# 12V_Converter.net
KiCad netlist of a schematic drawn in Altium Designer
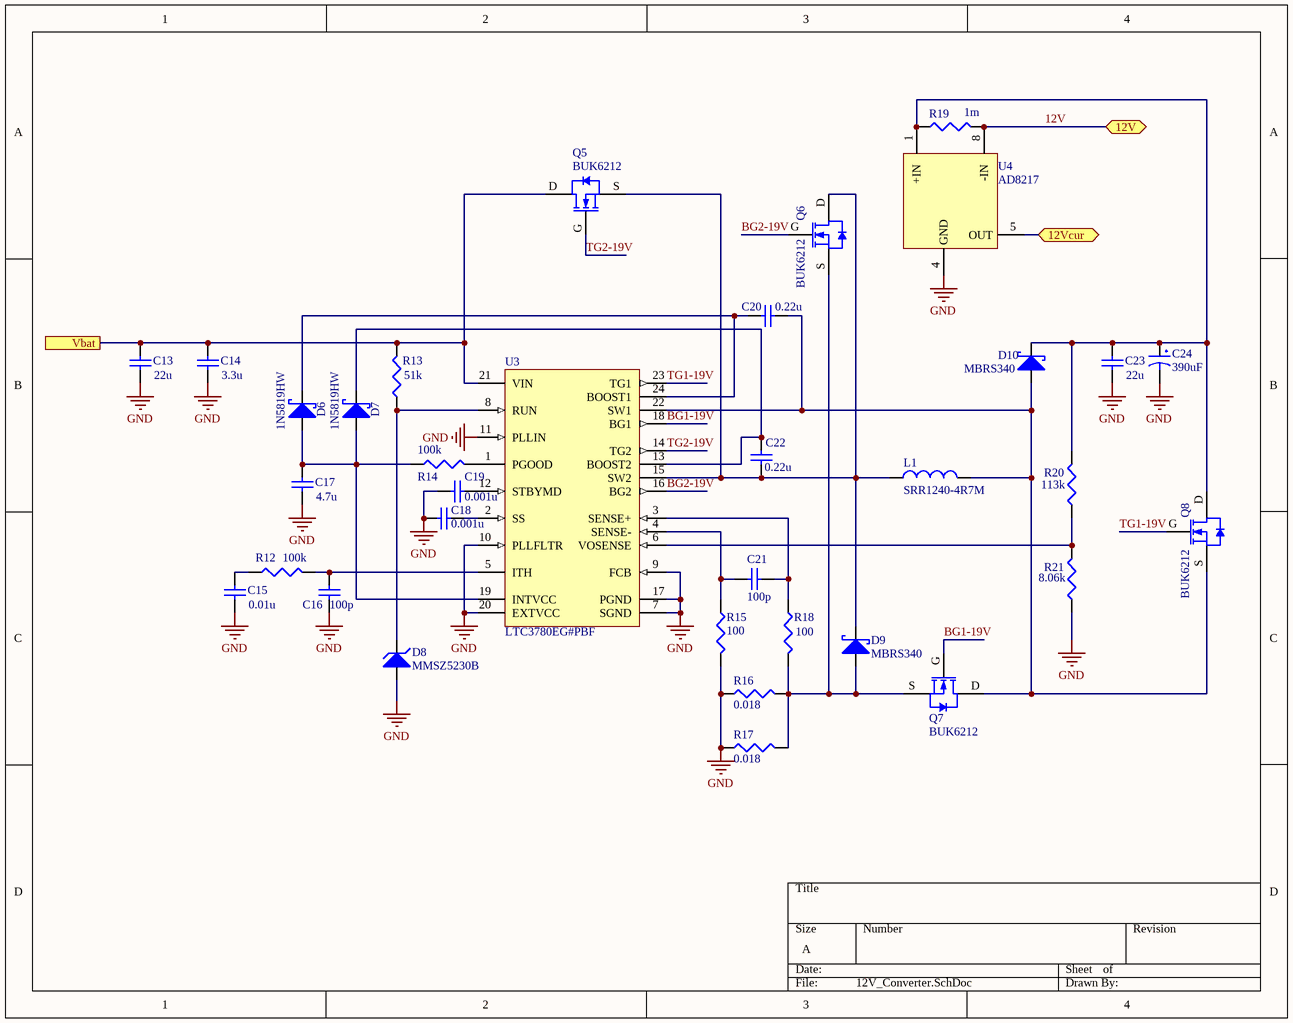
[diagram p0: 12V_Converter.SchDoc]

(export (version "E")
  (design (tool "Eeschema 10.0.6"))
  (components
    (comp (ref "C13")
      (value "22u")
      (footprint "C1206")
      (description "Capacitor (Semiconductor SIM Model)")
      (fields (field (name "Comment") "Cap Semi") (field (name "PUBLISHER") "Altium Limited"))
      (libsource (lib "Miscellaneous Devices") (part "Cap Semi"))
    )
    (comp (ref "C14")
      (value "3.3u")
      (footprint "C1206")
      (description "Capacitor (Semiconductor SIM Model)")
      (fields (field (name "Comment") "Cap Semi") (field (name "PUBLISHER") "Altium Limited"))
      (libsource (lib "Miscellaneous Devices") (part "Cap Semi"))
    )
    (comp (ref "C15")
      (value "0.01u")
      (footprint "C1206")
      (description "Capacitor (Semiconductor SIM Model)")
      (fields (field (name "Comment") "Cap Semi") (field (name "PUBLISHER") "Altium Limited"))
      (libsource (lib "Miscellaneous Devices") (part "Cap Semi"))
    )
    (comp (ref "C16")
      (value "100p")
      (footprint "C1206")
      (description "Capacitor (Semiconductor SIM Model)")
      (fields (field (name "Comment") "Cap Semi") (field (name "PUBLISHER") "Altium Limited"))
      (libsource (lib "Miscellaneous Devices") (part "Cap Semi"))
    )
    (comp (ref "C17")
      (value "4.7u")
      (footprint "C1206")
      (description "Capacitor (Semiconductor SIM Model)")
      (fields (field (name "Comment") "Cap Semi") (field (name "PUBLISHER") "Altium Limited"))
      (libsource (lib "Miscellaneous Devices") (part "Cap Semi"))
    )
    (comp (ref "C18")
      (value "0.001u")
      (footprint "C1206")
      (description "Capacitor (Semiconductor SIM Model)")
      (fields (field (name "Comment") "Cap Semi") (field (name "PUBLISHER") "Altium Limited"))
      (libsource (lib "Miscellaneous Devices") (part "Cap Semi"))
    )
    (comp (ref "C19")
      (value "0.001u")
      (footprint "C1206")
      (description "Capacitor (Semiconductor SIM Model)")
      (fields (field (name "Comment") "Cap Semi") (field (name "PUBLISHER") "Altium Limited"))
      (libsource (lib "Miscellaneous Devices") (part "Cap Semi"))
    )
    (comp (ref "C20")
      (value "0.22u")
      (footprint "C1206")
      (description "Capacitor (Semiconductor SIM Model)")
      (fields (field (name "Comment") "Cap Semi") (field (name "PUBLISHER") "Altium Limited"))
      (libsource (lib "Miscellaneous Devices") (part "Cap Semi"))
    )
    (comp (ref "C21")
      (value "100p")
      (footprint "C1206")
      (description "Capacitor (Semiconductor SIM Model)")
      (fields (field (name "Comment") "Cap Semi") (field (name "PUBLISHER") "Altium Limited"))
      (libsource (lib "Miscellaneous Devices") (part "Cap Semi"))
    )
    (comp (ref "C22")
      (value "0.22u")
      (footprint "C1206")
      (description "Capacitor (Semiconductor SIM Model)")
      (fields (field (name "Comment") "Cap Semi") (field (name "PUBLISHER") "Altium Limited"))
      (libsource (lib "Miscellaneous Devices") (part "Cap Semi"))
    )
    (comp (ref "C23")
      (value "22u")
      (footprint "C1206")
      (description "Capacitor (Semiconductor SIM Model)")
      (fields (field (name "Comment") "Cap Semi") (field (name "PUBLISHER") "Altium Limited"))
      (libsource (lib "Miscellaneous Devices") (part "Cap Semi"))
    )
    (comp (ref "C24")
      (value "390uF")
      (footprint "PCVxxxxxMCLxGS")
      (description "CAP ALUM POLY 390UF 20% 25V SMD")
      (libsource (lib "Power_Embedded_Board_Library") (part "PCV1E391MCL2GS"))
    )
    (comp (ref "D6")
      (value "1N5819HW")
      (footprint "1N58xx")
      (description "1A Schottky Barrier Rectifier Diode")
      (libsource (lib "Power_Embedded_Board_Library") (part "1N58xx"))
    )
    (comp (ref "D7")
      (value "1N5819HW")
      (footprint "1N58xx")
      (description "1A Schottky Barrier Rectifier Diode")
      (libsource (lib "Power_Embedded_Board_Library") (part "1N58xx"))
    )
    (comp (ref "D8")
      (value "MMSZ5230B")
      (footprint "ONSC-SOD-123-2-425-04_V")
      (description "Zener Voltage Regulator, 500 mW, 2-Pin SOD-123, Pb-Free, Tape and Reel")
      (fields (field (name "MANUFACTURER") "On Semiconductor") (field (name "PARTNUMBER") "MMSZ5230BT1G"))
      (libsource (lib "Power_Embedded_Board_Library") (part "MMSZ5230BT1G"))
    )
    (comp (ref "D9")
      (value "MBRS340")
      (footprint "MBRS340")
      (description "Schottky Rectifier")
      (libsource (lib "Power_Embedded_Board_Library") (part "MBRS340"))
    )
    (comp (ref "D10")
      (value "MBRS340")
      (footprint "MBRS340")
      (description "Schottky Rectifier")
      (libsource (lib "Power_Embedded_Board_Library") (part "MBRS340"))
    )
    (comp (ref "L1")
      (value "SRR1240-4R7M")
      (footprint "SRR1240")
      (description "FIXED IND 4.7UH 6A 18 MOHM SMD")
      (libsource (lib "Power_Embedded_Board_Library") (part "SRR1240"))
    )
    (comp (ref "Q5")
      (value "BUK6212")
      (footprint "NXP-SOT428_M")
      (description "N-Channel TrenchMOS Intermediate Level FET, 40 V, 50 A, 3-Pin SOT428, Tape and Reel")
      (fields
        (field (name "MANUFACTURER") "NXP Semiconductors")
        (field (name "PARTNUMBER") "BUK6212-40C,118")
      )
      (libsource (lib "Power_Embedded_Board_Library") (part "BUK6212"))
    )
    (comp (ref "Q6")
      (value "BUK6212")
      (footprint "NXP-SOT428_M")
      (description "N-Channel TrenchMOS Intermediate Level FET, 40 V, 50 A, 3-Pin SOT428, Tape and Reel")
      (fields
        (field (name "MANUFACTURER") "NXP Semiconductors")
        (field (name "PARTNUMBER") "BUK6212-40C,118")
      )
      (libsource (lib "Power_Embedded_Board_Library") (part "BUK6212"))
    )
    (comp (ref "Q7")
      (value "BUK6212")
      (footprint "NXP-SOT428_M")
      (description "N-Channel TrenchMOS Intermediate Level FET, 40 V, 50 A, 3-Pin SOT428, Tape and Reel")
      (fields
        (field (name "MANUFACTURER") "NXP Semiconductors")
        (field (name "PARTNUMBER") "BUK6212-40C,118")
      )
      (libsource (lib "Power_Embedded_Board_Library") (part "BUK6212"))
    )
    (comp (ref "Q8")
      (value "BUK6212")
      (footprint "NXP-SOT428_M")
      (description "N-Channel TrenchMOS Intermediate Level FET, 40 V, 50 A, 3-Pin SOT428, Tape and Reel")
      (fields
        (field (name "MANUFACTURER") "NXP Semiconductors")
        (field (name "PARTNUMBER") "BUK6212-40C,118")
      )
      (libsource (lib "Power_Embedded_Board_Library") (part "BUK6212"))
    )
    (comp (ref "R12")
      (value "100k")
      (footprint "J1-0603")
      (description "Resistor")
      (fields (field (name "Comment") "Res3") (field (name "PUBLISHER") "Altium Limited"))
      (libsource (lib "Miscellaneous Devices") (part "Res3"))
    )
    (comp (ref "R13")
      (value "51k")
      (footprint "J1-0603")
      (description "Resistor")
      (fields (field (name "Comment") "Res3") (field (name "PUBLISHER") "Altium Limited"))
      (libsource (lib "Miscellaneous Devices") (part "Res3"))
    )
    (comp (ref "R14")
      (value "100k")
      (footprint "J1-0603")
      (description "Resistor")
      (fields (field (name "Comment") "Res3") (field (name "PUBLISHER") "Altium Limited"))
      (libsource (lib "Miscellaneous Devices") (part "Res3"))
    )
    (comp (ref "R15")
      (value "100")
      (footprint "J1-0603")
      (description "Resistor")
      (fields (field (name "Comment") "Res3") (field (name "PUBLISHER") "Altium Limited"))
      (libsource (lib "Miscellaneous Devices") (part "Res3"))
    )
    (comp (ref "R16")
      (value "0.018")
      (footprint "R1206")
      (description "Resistor")
      (fields (field (name "Comment") "Res3") (field (name "PUBLISHER") "Altium Limited"))
      (libsource (lib "Miscellaneous Devices") (part "Res3"))
    )
    (comp (ref "R17")
      (value "0.018")
      (footprint "R1206")
      (description "Resistor")
      (fields (field (name "Comment") "Res3") (field (name "PUBLISHER") "Altium Limited"))
      (libsource (lib "Miscellaneous Devices") (part "Res3"))
    )
    (comp (ref "R18")
      (value "100")
      (footprint "J1-0603")
      (description "Resistor")
      (fields (field (name "Comment") "Res3") (field (name "PUBLISHER") "Altium Limited"))
      (libsource (lib "Miscellaneous Devices") (part "Res3"))
    )
    (comp (ref "R19")
      (value "1m")
      (footprint "14-1210")
      (description "Resistor")
      (fields (field (name "Comment") "Res3") (field (name "PUBLISHER") "Altium Limited"))
      (libsource (lib "Miscellaneous Devices") (part "Res3"))
    )
    (comp (ref "R20")
      (value "113k")
      (footprint "J1-0603")
      (description "Resistor")
      (fields (field (name "Comment") "Res3") (field (name "PUBLISHER") "Altium Limited"))
      (libsource (lib "Miscellaneous Devices") (part "Res3"))
    )
    (comp (ref "R21")
      (value "8.06k")
      (footprint "J1-0603")
      (description "Resistor")
      (fields (field (name "Comment") "Res3") (field (name "PUBLISHER") "Altium Limited"))
      (libsource (lib "Miscellaneous Devices") (part "Res3"))
    )
    (comp (ref "U3")
      (value "LTC3780EG#PBF")
      (footprint "LT-G-24_L")
      (fields (field (name "MANUFACTURER") "Linear Technology"))
      (libsource (lib "Power_Embedded_Board_Library") (part "LTC3780EG#PBF"))
    )
    (comp (ref "U4")
      (value "AD8217")
      (footprint "AD8217")
      (description "High Resolution, Zero-Drift  Current Shunt Monitor")
      (libsource (lib "Power_Embedded_Board_Library") (part "AD8217"))
    )
  )
  (nets
    (net (code "1") (name "/12V") (class "Default")
      (node (ref "R19") (pin "2") (pinfunction "2_2") (pintype "passive"))
      (node (ref "U4") (pin "8") (pinfunction "-IN_8") (pintype "passive"))
    )
    (net (code "2") (name "/12Vcur") (class "Default")
      (node (ref "U4") (pin "5") (pinfunction "OUT_5") (pintype "passive"))
    )
    (net (code "3") (name "/BG1-19V") (class "Default")
      (node (ref "Q7") (pin "G") (pinfunction "G_G") (pintype "passive"))
      (node (ref "U3") (pin "18") (pinfunction "BG1_18") (pintype "output"))
    )
    (net (code "4") (name "/BG2-19V") (class "Default")
      (node (ref "Q6") (pin "G") (pinfunction "G_G") (pintype "passive"))
      (node (ref "U3") (pin "16") (pinfunction "BG2_16") (pintype "output"))
    )
    (net (code "5") (name "/TG1-19V") (class "Default")
      (node (ref "Q8") (pin "G") (pinfunction "G_G") (pintype "passive"))
      (node (ref "U3") (pin "23") (pinfunction "TG1_23") (pintype "output"))
    )
    (net (code "6") (name "/TG2-19V") (class "Default")
      (node (ref "Q5") (pin "G") (pinfunction "G_G") (pintype "passive"))
      (node (ref "U3") (pin "14") (pinfunction "TG2_14") (pintype "output"))
    )
    (net (code "7") (name "/Vbat") (class "Default")
      (node (ref "C13") (pin "2") (pinfunction "2_2") (pintype "passive"))
      (node (ref "C14") (pin "2") (pinfunction "2_2") (pintype "passive"))
      (node (ref "Q5") (pin "D") (pinfunction "D_D") (pintype "passive"))
      (node (ref "R13") (pin "2") (pinfunction "2_2") (pintype "passive"))
      (node (ref "U3") (pin "21") (pinfunction "VIN_21") (pintype "power_in"))
    )
    (net (code "8") (name "GND") (class "Default")
      (node (ref "C13") (pin "1") (pinfunction "1_1") (pintype "passive"))
      (node (ref "C14") (pin "1") (pinfunction "1_1") (pintype "passive"))
      (node (ref "C15") (pin "1") (pinfunction "1_1") (pintype "passive"))
      (node (ref "C16") (pin "1") (pinfunction "1_1") (pintype "passive"))
      (node (ref "C17") (pin "1") (pinfunction "1_1") (pintype "passive"))
      (node (ref "C18") (pin "1") (pinfunction "1_1") (pintype "passive"))
      (node (ref "C19") (pin "1") (pinfunction "1_1") (pintype "passive"))
      (node (ref "C23") (pin "1") (pinfunction "1_1") (pintype "passive"))
      (node (ref "C24") (pin "2") (pinfunction "2_2") (pintype "passive"))
      (node (ref "D8") (pin "2") (pinfunction "A_2") (pintype "passive"))
      (node (ref "R15") (pin "2") (pinfunction "2_2") (pintype "passive"))
      (node (ref "R16") (pin "1") (pinfunction "1_1") (pintype "passive"))
      (node (ref "R17") (pin "1") (pinfunction "1_1") (pintype "passive"))
      (node (ref "R21") (pin "1") (pinfunction "1_1") (pintype "passive"))
      (node (ref "U3") (pin "10") (pinfunction "PLLFLTR_10") (pintype "input"))
      (node (ref "U3") (pin "11") (pinfunction "PLLIN_11") (pintype "input"))
      (node (ref "U3") (pin "17") (pinfunction "PGND_17") (pintype "power_in"))
      (node (ref "U3") (pin "20") (pinfunction "EXTVCC_20") (pintype "power_in"))
      (node (ref "U3") (pin "7") (pinfunction "SGND_7") (pintype "power_in"))
      (node (ref "U3") (pin "9") (pinfunction "FCB_9") (pintype "input"))
      (node (ref "U4") (pin "4") (pinfunction "GND_4") (pintype "passive"))
    )
    (net (code "9") (name "Net-(C15-Pad2)") (class "Default")
      (node (ref "C15") (pin "2") (pinfunction "2_2") (pintype "passive"))
      (node (ref "R12") (pin "1") (pinfunction "1_1") (pintype "passive"))
    )
    (net (code "10") (name "Net-(D6-Anode)") (class "Default")
      (node (ref "C17") (pin "2") (pinfunction "2_2") (pintype "passive"))
      (node (ref "D6") (pin "A") (pinfunction "Anode_A") (pintype "passive"))
      (node (ref "D7") (pin "A") (pinfunction "Anode_A") (pintype "passive"))
      (node (ref "R14") (pin "1") (pinfunction "1_1") (pintype "passive"))
      (node (ref "U3") (pin "19") (pinfunction "INTVCC_19") (pintype "power_in"))
    )
    (net (code "11") (name "Net-(D6-Cathode)") (class "Default")
      (node (ref "C20") (pin "2") (pinfunction "2_2") (pintype "passive"))
      (node (ref "D6") (pin "K") (pinfunction "Cathode_K") (pintype "passive"))
      (node (ref "U3") (pin "24") (pinfunction "BOOST1_24") (pintype "passive"))
    )
    (net (code "12") (name "Net-(D7-Cathode)") (class "Default")
      (node (ref "C22") (pin "2") (pinfunction "2_2") (pintype "passive"))
      (node (ref "D7") (pin "K") (pinfunction "Cathode_K") (pintype "passive"))
      (node (ref "U3") (pin "13") (pinfunction "BOOST2_13") (pintype "passive"))
    )
    (net (code "13") (name "Net-(D8-K)") (class "Default")
      (node (ref "D8") (pin "1") (pinfunction "K_1") (pintype "passive"))
      (node (ref "R13") (pin "1") (pinfunction "1_1") (pintype "passive"))
      (node (ref "U3") (pin "8") (pinfunction "RUN_8") (pintype "input"))
    )
    (net (code "14") (name "Net-(D9-Anode)") (class "Default")
      (node (ref "D9") (pin "A") (pinfunction "Anode_A") (pintype "passive"))
      (node (ref "Q6") (pin "S") (pinfunction "S_S") (pintype "passive"))
      (node (ref "Q7") (pin "S") (pinfunction "S_S") (pintype "passive"))
      (node (ref "R16") (pin "2") (pinfunction "2_2") (pintype "passive"))
      (node (ref "R17") (pin "2") (pinfunction "2_2") (pintype "passive"))
      (node (ref "R18") (pin "2") (pinfunction "2_2") (pintype "passive"))
    )
    (net (code "15") (name "Net-(D9-Cathode)") (class "Default")
      (node (ref "C22") (pin "1") (pinfunction "1_1") (pintype "passive"))
      (node (ref "D9") (pin "K") (pinfunction "Cathode_K") (pintype "passive"))
      (node (ref "L1") (pin "1") (pinfunction "1_1") (pintype "passive"))
      (node (ref "Q5") (pin "S") (pinfunction "S_S") (pintype "passive"))
      (node (ref "Q6") (pin "D") (pinfunction "D_D") (pintype "passive"))
      (node (ref "U3") (pin "15") (pinfunction "SW2_15") (pintype "passive"))
    )
    (net (code "16") (name "Net-(D10-Anode)") (class "Default")
      (node (ref "C20") (pin "1") (pinfunction "1_1") (pintype "passive"))
      (node (ref "D10") (pin "A") (pinfunction "Anode_A") (pintype "passive"))
      (node (ref "L1") (pin "2") (pinfunction "2_2") (pintype "passive"))
      (node (ref "Q7") (pin "D") (pinfunction "D_D") (pintype "passive"))
      (node (ref "Q8") (pin "S") (pinfunction "S_S") (pintype "passive"))
      (node (ref "U3") (pin "22") (pinfunction "SW1_22") (pintype "passive"))
    )
    (net (code "17") (name "Net-(D10-Cathode)") (class "Default")
      (node (ref "C23") (pin "2") (pinfunction "2_2") (pintype "passive"))
      (node (ref "C24") (pin "1") (pinfunction "1_1") (pintype "passive"))
      (node (ref "D10") (pin "K") (pinfunction "Cathode_K") (pintype "passive"))
      (node (ref "Q8") (pin "D") (pinfunction "D_D") (pintype "passive"))
      (node (ref "R19") (pin "1") (pinfunction "1_1") (pintype "passive"))
      (node (ref "R20") (pin "2") (pinfunction "2_2") (pintype "passive"))
      (node (ref "U4") (pin "1") (pinfunction "+IN_1") (pintype "passive"))
    )
    (net (code "18") (name "Net-(U3-ITH)") (class "Default")
      (node (ref "C16") (pin "2") (pinfunction "2_2") (pintype "passive"))
      (node (ref "R12") (pin "2") (pinfunction "2_2") (pintype "passive"))
      (node (ref "U3") (pin "5") (pinfunction "ITH_5") (pintype "passive"))
    )
    (net (code "19") (name "Net-(U3-PGOOD)") (class "Default")
      (node (ref "R14") (pin "2") (pinfunction "2_2") (pintype "passive"))
      (node (ref "U3") (pin "1") (pinfunction "PGOOD_1") (pintype "open_collector"))
    )
    (net (code "20") (name "Net-(U3-SENSE+)") (class "Default")
      (node (ref "C21") (pin "2") (pinfunction "2_2") (pintype "passive"))
      (node (ref "R18") (pin "1") (pinfunction "1_1") (pintype "passive"))
      (node (ref "U3") (pin "3") (pinfunction "SENSE+_3") (pintype "input"))
    )
    (net (code "21") (name "Net-(U3-SENSE-)") (class "Default")
      (node (ref "C21") (pin "1") (pinfunction "1_1") (pintype "passive"))
      (node (ref "R15") (pin "1") (pinfunction "1_1") (pintype "passive"))
      (node (ref "U3") (pin "4") (pinfunction "SENSE-_4") (pintype "input"))
    )
    (net (code "22") (name "Net-(U3-SS)") (class "Default")
      (node (ref "C18") (pin "2") (pinfunction "2_2") (pintype "passive"))
      (node (ref "U3") (pin "2") (pinfunction "SS_2") (pintype "input"))
    )
    (net (code "23") (name "Net-(U3-STBYMD)") (class "Default")
      (node (ref "C19") (pin "2") (pinfunction "2_2") (pintype "passive"))
      (node (ref "U3") (pin "12") (pinfunction "STBYMD_12") (pintype "input"))
    )
    (net (code "24") (name "Net-(U3-VOSENSE)") (class "Default")
      (node (ref "R20") (pin "1") (pinfunction "1_1") (pintype "passive"))
      (node (ref "R21") (pin "2") (pinfunction "2_2") (pintype "passive"))
      (node (ref "U3") (pin "6") (pinfunction "VOSENSE_6") (pintype "input"))
    )
  )
)
